# SilSpark.net
KiCad netlist of a schematic drawn in EAGLE
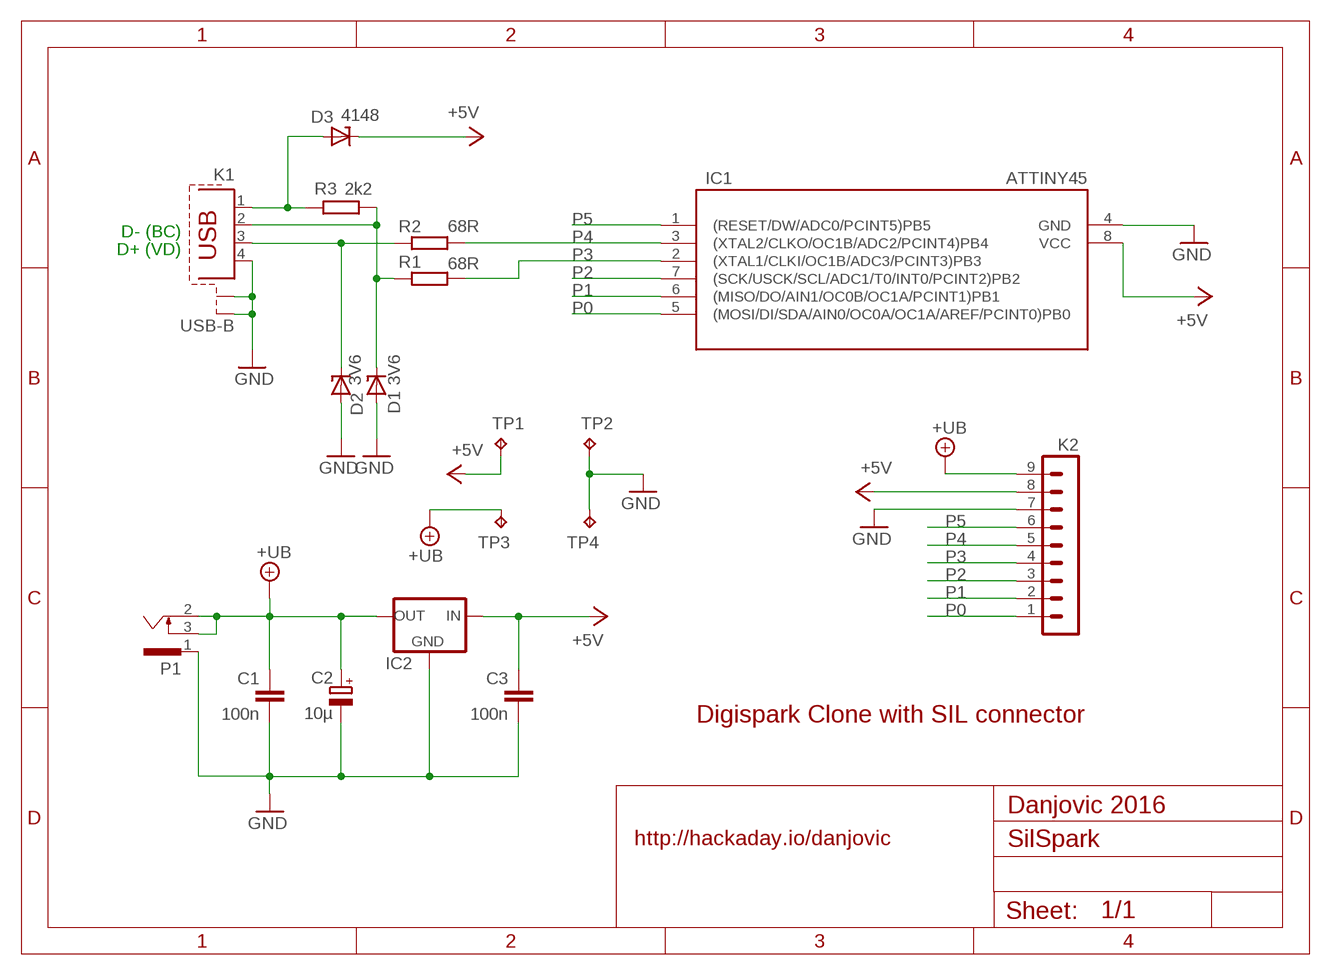
[diagram p0: schematic, sheet 1]

(export (version "E")
  (design (tool "Eeschema 10.0.6"))
  (components
    (comp (ref "C1")
      (value "100n")
      (footprint "eagle-import:C050-025X075_LARGEPADS")
      (libsource (lib "eagle-import") (part "C-EU050-025X075_LARGEPADS"))
    )
    (comp (ref "C2")
      (value "10µ")
      (footprint "eagle-import:E2-4_LARGEPADS")
      (libsource (lib "eagle-import") (part "CPOL-EUE2-4_LARGEPADS"))
    )
    (comp (ref "C3")
      (value "100n")
      (footprint "eagle-import:C050-025X075_LARGEPADS")
      (libsource (lib "eagle-import") (part "C-EU050-025X075_LARGEPADS"))
    )
    (comp (ref "D1")
      (value "3V6")
      (footprint "eagle-import:ZDIO-5_LARGEPADS")
      (libsource (lib "eagle-import") (part "ZENER-DIODEZDIO-5_LARGEPADS"))
    )
    (comp (ref "D2")
      (value "3V6")
      (footprint "eagle-import:ZDIO-5_LARGEPADS")
      (libsource (lib "eagle-import") (part "ZENER-DIODEZDIO-5_LARGEPADS"))
    )
    (comp (ref "D3")
      (value "4148")
      (footprint "eagle-import:ZDIO-5_LARGEPADS")
      (libsource (lib "eagle-import") (part "ZENER-DIODEZDIO-5_LARGEPADS"))
    )
    (comp (ref "IC1")
      (value "ATTINY45")
      (footprint "eagle-import:DIL08")
      (libsource (lib "eagle-import") (part "ATTINY45P-20"))
    )
    (comp (ref "IC2")
      (value "78LXXFLAT")
      (footprint "eagle-import:VREG-TO90FLAT")
      (libsource (lib "eagle-import") (part "78LXXFLAT"))
    )
    (comp (ref "K1")
      (value "USB-B")
      (footprint "eagle-import:PN61729-S_LARGEPADS")
      (libsource (lib "eagle-import") (part "PN61729-SLARGEPADS"))
    )
    (comp (ref "K2")
      (value "MA09-1W")
      (footprint "eagle-import:MA09-1W")
      (libsource (lib "eagle-import") (part "MA09-1W"))
    )
    (comp (ref "P1")
      (value "733989-5")
      (footprint "eagle-import:733989-5")
      (libsource (lib "eagle-import") (part "73398?9-5"))
    )
    (comp (ref "R1")
      (value "68R")
      (footprint "eagle-import:0204_7_LARGEPADS")
      (libsource (lib "eagle-import") (part "R-EU_0207/7_LARGEPADS"))
    )
    (comp (ref "R2")
      (value "68R")
      (footprint "eagle-import:0204_7_LARGEPADS")
      (libsource (lib "eagle-import") (part "R-EU_0207/7_LARGEPADS"))
    )
    (comp (ref "R3")
      (value "2k2")
      (footprint "eagle-import:0204_7_LARGEPADS")
      (libsource (lib "eagle-import") (part "R-EU_0207/7_LARGEPADS"))
    )
    (comp (ref "TP1")
      (value "TPPAD1-13")
      (footprint "eagle-import:P1-13")
      (libsource (lib "eagle-import") (part "TPPAD1-13"))
    )
    (comp (ref "TP2")
      (value "TPPAD1-13")
      (footprint "eagle-import:P1-13")
      (libsource (lib "eagle-import") (part "TPPAD1-13"))
    )
    (comp (ref "TP3")
      (value "TPPAD1-13")
      (footprint "eagle-import:P1-13")
      (libsource (lib "eagle-import") (part "TPPAD1-13"))
    )
    (comp (ref "TP4")
      (value "TPPAD1-13")
      (footprint "eagle-import:P1-13")
      (libsource (lib "eagle-import") (part "TPPAD1-13"))
    )
  )
  (nets
    (net (code "1") (name "+5V") (class "Default")
      (node (ref "C3") (pin "1") (pinfunction "1_1") (pintype "passive"))
      (node (ref "D3") (pin "C") (pinfunction "C_C") (pintype "passive"))
      (node (ref "IC1") (pin "8") (pinfunction "VCC_8") (pintype "bidirectional"))
      (node (ref "IC2") (pin "IN") (pinfunction "IN_IN") (pintype "input"))
      (node (ref "K2") (pin "8") (pinfunction "8_8") (pintype "passive"))
      (node (ref "TP1") (pin "TP") (pinfunction "TP_TP") (pintype "input"))
    )
    (net (code "2") (name "+UB") (class "Default")
      (node (ref "C1") (pin "1") (pinfunction "1_1") (pintype "passive"))
      (node (ref "C2") (pin "+") (pinfunction "+_+") (pintype "passive"))
      (node (ref "IC2") (pin "OUT") (pinfunction "OUT_OUT") (pintype "passive"))
      (node (ref "K2") (pin "9") (pinfunction "9_9") (pintype "passive"))
      (node (ref "P1") (pin "2") (pinfunction "2_2") (pintype "passive"))
      (node (ref "P1") (pin "3") (pinfunction "3_3") (pintype "passive"))
      (node (ref "TP3") (pin "TP") (pinfunction "TP_TP") (pintype "input"))
    )
    (net (code "3") (name "/P0") (class "Default")
      (node (ref "IC1") (pin "5") (pinfunction "(MOSI/DI/SDA/AIN0/OC0A/OC1A/AREF/PCINT0)PB0_5") (pintype "bidirectional"))
      (node (ref "K2") (pin "1") (pinfunction "1_1") (pintype "passive"))
    )
    (net (code "4") (name "/P1") (class "Default")
      (node (ref "IC1") (pin "6") (pinfunction "(MISO/DO/AIN1/OC0B/OC1A/PCINT1)PB1_6") (pintype "bidirectional"))
      (node (ref "K2") (pin "2") (pinfunction "2_2") (pintype "passive"))
    )
    (net (code "5") (name "/P2") (class "Default")
      (node (ref "IC1") (pin "7") (pinfunction "(SCK/USCK/SCL/ADC1/T0/INT0/PCINT2)PB2_7") (pintype "bidirectional"))
      (node (ref "K2") (pin "3") (pinfunction "3_3") (pintype "passive"))
    )
    (net (code "6") (name "/P3") (class "Default")
      (node (ref "IC1") (pin "2") (pinfunction "(XTAL1/CLKI/OC1B/ADC3/PCINT3)PB3_2") (pintype "bidirectional"))
      (node (ref "K2") (pin "4") (pinfunction "4_4") (pintype "passive"))
      (node (ref "R1") (pin "1") (pinfunction "1_1") (pintype "passive"))
    )
    (net (code "7") (name "/P4") (class "Default")
      (node (ref "IC1") (pin "3") (pinfunction "(XTAL2/CLKO/OC1B/ADC2/PCINT4)PB4_3") (pintype "bidirectional"))
      (node (ref "K2") (pin "5") (pinfunction "5_5") (pintype "passive"))
      (node (ref "R2") (pin "1") (pinfunction "1_1") (pintype "passive"))
    )
    (net (code "8") (name "/P5") (class "Default")
      (node (ref "IC1") (pin "1") (pinfunction "(RESET/DW/ADC0/PCINT5)PB5_1") (pintype "bidirectional"))
      (node (ref "K2") (pin "6") (pinfunction "6_6") (pintype "passive"))
    )
    (net (code "9") (name "GND") (class "Default")
      (node (ref "C1") (pin "2") (pinfunction "2_2") (pintype "passive"))
      (node (ref "C2") (pin "-") (pinfunction "-_-") (pintype "passive"))
      (node (ref "C3") (pin "2") (pinfunction "2_2") (pintype "passive"))
      (node (ref "D1") (pin "A") (pinfunction "A_A") (pintype "passive"))
      (node (ref "D2") (pin "A") (pinfunction "A_A") (pintype "passive"))
      (node (ref "IC1") (pin "4") (pinfunction "GND_4") (pintype "bidirectional"))
      (node (ref "IC2") (pin "GND") (pinfunction "GND_GND") (pintype "input"))
      (node (ref "K1") (pin "4") (pinfunction "4_4") (pintype "passive"))
      (node (ref "K1") (pin "S1") (pinfunction "S1_S1") (pintype "passive"))
      (node (ref "K1") (pin "S2") (pinfunction "S2_S2") (pintype "passive"))
      (node (ref "K2") (pin "7") (pinfunction "7_7") (pintype "passive"))
      (node (ref "P1") (pin "1") (pinfunction "1_1") (pintype "passive"))
      (node (ref "TP2") (pin "TP") (pinfunction "TP_TP") (pintype "input"))
      (node (ref "TP4") (pin "TP") (pinfunction "TP_TP") (pintype "input"))
    )
    (net (code "10") (name "Net-(D1-PadC)") (class "Default")
      (node (ref "D1") (pin "C") (pinfunction "C_C") (pintype "passive"))
      (node (ref "K1") (pin "2") (pinfunction "2_2") (pintype "passive"))
      (node (ref "R1") (pin "2") (pinfunction "2_2") (pintype "passive"))
      (node (ref "R3") (pin "2") (pinfunction "2_2") (pintype "passive"))
    )
    (net (code "11") (name "Net-(D2-PadC)") (class "Default")
      (node (ref "D2") (pin "C") (pinfunction "C_C") (pintype "passive"))
      (node (ref "K1") (pin "3") (pinfunction "3_3") (pintype "passive"))
      (node (ref "R2") (pin "2") (pinfunction "2_2") (pintype "passive"))
    )
    (net (code "12") (name "Net-(D3-PadA)") (class "Default")
      (node (ref "D3") (pin "A") (pinfunction "A_A") (pintype "passive"))
      (node (ref "K1") (pin "1") (pinfunction "1_1") (pintype "passive"))
      (node (ref "R3") (pin "1") (pinfunction "1_1") (pintype "passive"))
    )
  )
)
